# 18_-WIFI_MODULE.net
KiCad netlist of a schematic drawn in Altium Designer
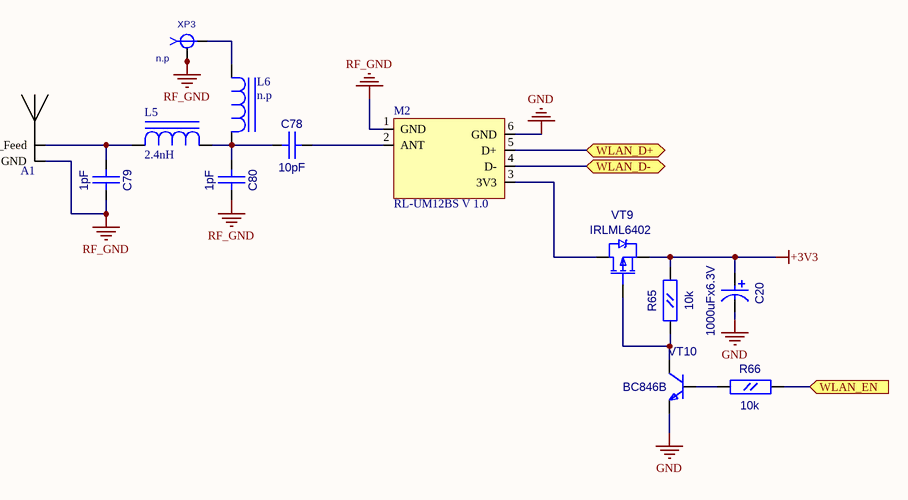
[diagram p0: [18]-WIFI_MODULE.SchDoc]

(export (version "E")
  (design (tool "Eeschema 10.0.6"))
  (components
    (comp (ref "A1")
      (value "Antenna Wi-Fi")
      (footprint "Antenna_WiFi")
      (description "2.43GHz")
      (libsource (lib "fizik_lib") (part "Antenna Wi-Fi"))
    )
    (comp (ref "C20")
      (value "1000uFx6.3V")
      (footprint "CC8X11.5_L")
      (description "Radial capacitor")
      (libsource (lib "fizik_lib") (part "CAP_8mm"))
    )
    (comp (ref "C78")
      (value "10pF")
      (footprint "CC0603")
      (description "CC0603")
      (libsource (lib "gprs_modem_2") (part "CC0603"))
    )
    (comp (ref "C79")
      (value "1pF")
      (footprint "CC0603")
      (description "CC0603")
      (libsource (lib "gprs_modem_2") (part "CC0603"))
    )
    (comp (ref "C80")
      (value "1pF")
      (footprint "CC0603")
      (description "CC0603")
      (libsource (lib "gprs_modem_2") (part "CC0603"))
    )
    (comp (ref "L5")
      (value "2.4nH")
      (footprint "L0402")
      (description "L0402")
      (libsource (lib "gprs_modem_2") (part "L0402"))
    )
    (comp (ref "L6")
      (value "n.p")
      (footprint "L0402")
      (description "L0402")
      (libsource (lib "gprs_modem_2") (part "L0402"))
    )
    (comp (ref "M2")
      (value "RL-UM12BS V 1.0")
      (footprint "RTL8188_MODULE")
      (libsource (lib "fizik_lib") (part "RTL8188_MODULE"))
    )
    (comp (ref "R65")
      (value "10k")
      (footprint "RC0603")
      (description "RC0603")
      (libsource (lib "gprs_modem_2") (part "RC0603"))
    )
    (comp (ref "R66")
      (value "10k")
      (footprint "RC0603")
      (description "RC0603")
      (libsource (lib "gprs_modem_2") (part "RC0603"))
    )
    (comp (ref "VT9")
      (value "IRLML6402")
      (footprint "SOT-23(123)")
      (description "HEXFET Power MOSFET")
      (libsource (lib "gprs_modem_2") (part "IRLML6402"))
    )
    (comp (ref "VT10")
      (value "BC846B")
      (footprint "SOT-23(123)")
      (description "BC846BLT1")
      (libsource (lib "gprs_modem_2") (part "BC846BLT1"))
    )
    (comp (ref "XP3")
      (value "n.p")
      (footprint "SMA-JR")
      (description "SMA-JR")
      (libsource (lib "fizik_lib") (part "SMA-JR"))
    )
  )
  (nets
    (net (code "1") (name "+3V3") (class "Default")
      (node (ref "C20") (pin "1") (pintype "passive"))
      (node (ref "R65") (pin "2") (pinfunction "B_2") (pintype "passive"))
      (node (ref "VT9") (pin "2") (pinfunction "S_2") (pintype "passive"))
    )
    (net (code "2") (name "/WLAN_D+") (class "Default")
      (node (ref "M2") (pin "5") (pinfunction "D+_5") (pintype "passive"))
    )
    (net (code "3") (name "/WLAN_D-") (class "Default")
      (node (ref "M2") (pin "4") (pinfunction "D-_4") (pintype "passive"))
    )
    (net (code "4") (name "/WLAN_EN") (class "Default")
      (node (ref "R66") (pin "2") (pinfunction "B_2") (pintype "passive"))
    )
    (net (code "5") (name "GND") (class "Default")
      (node (ref "C20") (pin "2") (pintype "passive"))
      (node (ref "M2") (pin "6") (pinfunction "GND_6") (pintype "passive"))
      (node (ref "VT10") (pin "2") (pinfunction "E_2") (pintype "passive"))
    )
    (net (code "6") (name "Net-(A1-RF_Feed)") (class "Default")
      (node (ref "A1") (pin "1") (pinfunction "RF_Feed_1") (pintype "passive"))
      (node (ref "C79") (pin "1") (pinfunction "A_1") (pintype "passive"))
      (node (ref "L5") (pin "1") (pinfunction "A_1") (pintype "passive"))
    )
    (net (code "7") (name "Net-(C78-A)") (class "Default")
      (node (ref "C78") (pin "1") (pinfunction "A_1") (pintype "passive"))
      (node (ref "C80") (pin "1") (pinfunction "A_1") (pintype "passive"))
      (node (ref "L5") (pin "2") (pinfunction "C_2") (pintype "passive"))
      (node (ref "L6") (pin "2") (pinfunction "C_2") (pintype "passive"))
    )
    (net (code "8") (name "Net-(C78-B)") (class "Default")
      (node (ref "C78") (pin "2") (pinfunction "B_2") (pintype "passive"))
      (node (ref "M2") (pin "2") (pinfunction "ANT_2") (pintype "passive"))
    )
    (net (code "9") (name "Net-(L6-A)") (class "Default")
      (node (ref "L6") (pin "1") (pinfunction "A_1") (pintype "passive"))
      (node (ref "XP3") (pin "1") (pintype "passive"))
    )
    (net (code "10") (name "Net-(M2-3V3)") (class "Default")
      (node (ref "M2") (pin "3") (pinfunction "3V3_3") (pintype "passive"))
      (node (ref "VT9") (pin "3") (pinfunction "D_3") (pintype "passive"))
    )
    (net (code "11") (name "Net-(R65-A)") (class "Default")
      (node (ref "R65") (pin "1") (pinfunction "A_1") (pintype "passive"))
      (node (ref "VT10") (pin "3") (pinfunction "C_3") (pintype "passive"))
      (node (ref "VT9") (pin "1") (pinfunction "G_1") (pintype "passive"))
    )
    (net (code "12") (name "Net-(R66-A)") (class "Default")
      (node (ref "R66") (pin "1") (pinfunction "A_1") (pintype "passive"))
      (node (ref "VT10") (pin "1") (pinfunction "B_1") (pintype "passive"))
    )
    (net (code "13") (name "RF_GND") (class "Default")
      (node (ref "A1") (pin "2") (pinfunction "GND_2") (pintype "passive"))
      (node (ref "C79") (pin "2") (pinfunction "B_2") (pintype "passive"))
      (node (ref "C80") (pin "2") (pinfunction "B_2") (pintype "passive"))
      (node (ref "M2") (pin "1") (pinfunction "GND_1") (pintype "passive"))
      (node (ref "XP3") (pin "2") (pintype "passive"))
      (node (ref "XP3") (pin "3") (pintype "passive"))
      (node (ref "XP3") (pin "4") (pintype "passive"))
      (node (ref "XP3") (pin "5") (pintype "passive"))
    )
  )
)
